# fuente1.net
KiCad netlist of a schematic drawn in Altium Designer
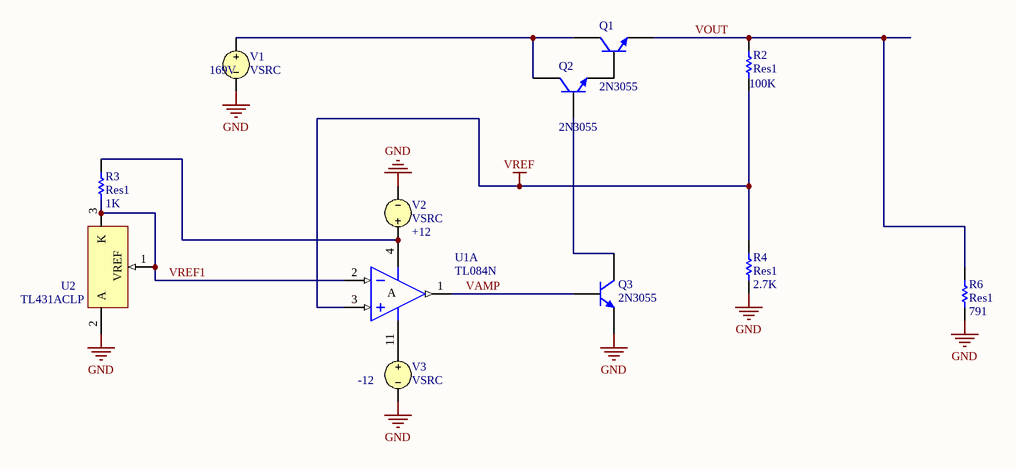
[diagram p0: fuente1.SchDoc]

(export (version "E")
  (design (tool "Eeschema 10.0.6"))
  (components
    (comp (ref "Q1")
      (value "2N3055")
      (footprint "TO-3")
      (description "Complementary Silicon Power Transistor")
      (fields (field (name "PUBLISHER") "Altium Limited"))
      (libsource (lib "ST Discrete BJT") (part "2N3055"))
    )
    (comp (ref "Q2")
      (value "2N3055")
      (footprint "TO-3")
      (description "Complementary Silicon Power Transistor")
      (fields (field (name "PUBLISHER") "Altium Limited"))
      (libsource (lib "ST Discrete BJT") (part "2N3055"))
    )
    (comp (ref "Q3")
      (value "2N3055")
      (footprint "TO-3")
      (description "Complementary Silicon Power Transistor")
      (fields (field (name "PUBLISHER") "Altium Limited"))
      (libsource (lib "ST Discrete BJT") (part "2N3055"))
    )
    (comp (ref "R2")
      (value "Res1")
      (footprint "AXIAL-0.3")
      (description "Resistor")
      (fields (field (name "ALTIUM_VALUE") "100K") (field (name "PUBLISHER") "Altium Limited"))
      (libsource (lib "Miscellaneous Devices") (part "Res1"))
    )
    (comp (ref "R3")
      (value "Res1")
      (footprint "AXIAL-0.3")
      (description "Resistor")
      (fields (field (name "ALTIUM_VALUE") "1K") (field (name "PUBLISHER") "Altium Limited"))
      (libsource (lib "Miscellaneous Devices") (part "Res1"))
    )
    (comp (ref "R4")
      (value "Res1")
      (footprint "AXIAL-0.3")
      (description "Resistor")
      (fields (field (name "ALTIUM_VALUE") "2.7K") (field (name "PUBLISHER") "Altium Limited"))
      (libsource (lib "Miscellaneous Devices") (part "Res1"))
    )
    (comp (ref "R6")
      (value "Res1")
      (footprint "AXIAL-0.3")
      (description "Resistor")
      (fields (field (name "ALTIUM_VALUE") "791") (field (name "PUBLISHER") "Altium Limited"))
      (libsource (lib "Miscellaneous Devices") (part "Res1"))
    )
    (comp (ref "U1")
      (value "TL084N")
      (footprint "N014")
      (description "JFET-Input Operational Amplifier")
      (fields (field (name "PUBLISHER") "Altium Limited"))
      (libsource (lib "TI Operational Amplifier") (part "TL084N"))
    )
    (comp (ref "U2")
      (value "TL431ACLP")
      (footprint "LP03")
      (description "Adjustable Precision Shunt Regulator")
      (fields (field (name "PUBLISHER") "Altium Limited"))
      (libsource (lib "TI Power Mgt Voltage Regulator") (part "TL431ACLP"))
    )
    (comp (ref "V1")
      (value "VSRC")
      (description "Voltage Source")
      (fields (field (name "ALTIUM_VALUE") "169V") (field (name "PUBLISHER") "Altium Limited"))
      (libsource (lib "Simulation Sources") (part "VSRC"))
    )
    (comp (ref "V2")
      (value "VSRC")
      (description "Voltage Source")
      (fields (field (name "ALTIUM_VALUE") "+12") (field (name "PUBLISHER") "Altium Limited"))
      (libsource (lib "Simulation Sources") (part "VSRC"))
    )
    (comp (ref "V3")
      (value "VSRC")
      (description "Voltage Source")
      (fields (field (name "ALTIUM_VALUE") "-12") (field (name "PUBLISHER") "Altium Limited"))
      (libsource (lib "Simulation Sources") (part "VSRC"))
    )
  )
  (nets
    (net (code "1") (name "/VAMP") (class "Default")
      (node (ref "Q3") (pin "1") (pinfunction "B_1") (pintype "passive"))
      (node (ref "U1") (pin "1") (pinfunction "OUT_1") (pintype "output"))
    )
    (net (code "2") (name "/VOUT") (class "Default")
      (node (ref "Q1") (pin "2") (pinfunction "E_2") (pintype "passive"))
      (node (ref "R2") (pin "2") (pinfunction "2_2") (pintype "passive"))
      (node (ref "R6") (pin "2") (pinfunction "2_2") (pintype "passive"))
    )
    (net (code "3") (name "/VREF1") (class "Default")
      (node (ref "R3") (pin "1") (pinfunction "1_1") (pintype "passive"))
      (node (ref "U1") (pin "2") (pinfunction "IN-_2") (pintype "input"))
      (node (ref "U2") (pin "1") (pinfunction "VREF_1") (pintype "input"))
      (node (ref "U2") (pin "3") (pinfunction "K_3") (pintype "power_in"))
    )
    (net (code "4") (name "GND") (class "Default")
      (node (ref "Q3") (pin "2") (pinfunction "E_2") (pintype "passive"))
      (node (ref "R4") (pin "1") (pinfunction "1_1") (pintype "passive"))
      (node (ref "R6") (pin "1") (pinfunction "1_1") (pintype "passive"))
      (node (ref "U2") (pin "2") (pinfunction "A_2") (pintype "power_in"))
      (node (ref "V1") (pin "2") (pinfunction "2_2") (pintype "passive"))
      (node (ref "V2") (pin "2") (pinfunction "2_2") (pintype "passive"))
      (node (ref "V3") (pin "2") (pinfunction "2_2") (pintype "passive"))
    )
    (net (code "5") (name "Net-(Q1-B)") (class "Default")
      (node (ref "Q1") (pin "1") (pinfunction "B_1") (pintype "passive"))
      (node (ref "Q2") (pin "2") (pinfunction "E_2") (pintype "passive"))
    )
    (net (code "6") (name "Net-(Q1-C)") (class "Default")
      (node (ref "Q1") (pin "3") (pinfunction "C_3") (pintype "passive"))
      (node (ref "Q2") (pin "3") (pinfunction "C_3") (pintype "passive"))
      (node (ref "V1") (pin "1") (pinfunction "1_1") (pintype "passive"))
    )
    (net (code "7") (name "Net-(Q2-B)") (class "Default")
      (node (ref "Q2") (pin "1") (pinfunction "B_1") (pintype "passive"))
      (node (ref "Q3") (pin "3") (pinfunction "C_3") (pintype "passive"))
    )
    (net (code "8") (name "Net-(U1A-V+)") (class "Default")
      (node (ref "R3") (pin "2") (pinfunction "2_2") (pintype "passive"))
      (node (ref "U1") (pin "4") (pinfunction "V+_4") (pintype "power_in"))
      (node (ref "V2") (pin "1") (pinfunction "1_1") (pintype "passive"))
    )
    (net (code "9") (name "Net-(U1A-V-)") (class "Default")
      (node (ref "U1") (pin "11") (pinfunction "V-_11") (pintype "power_in"))
      (node (ref "V3") (pin "1") (pinfunction "1_1") (pintype "passive"))
    )
    (net (code "10") (name "VREF") (class "Default")
      (node (ref "R2") (pin "1") (pinfunction "1_1") (pintype "passive"))
      (node (ref "R4") (pin "2") (pinfunction "2_2") (pintype "passive"))
      (node (ref "U1") (pin "3") (pinfunction "IN+_3") (pintype "input"))
    )
  )
)
